# power_supplies.net
KiCad netlist of a schematic drawn in Altium Designer
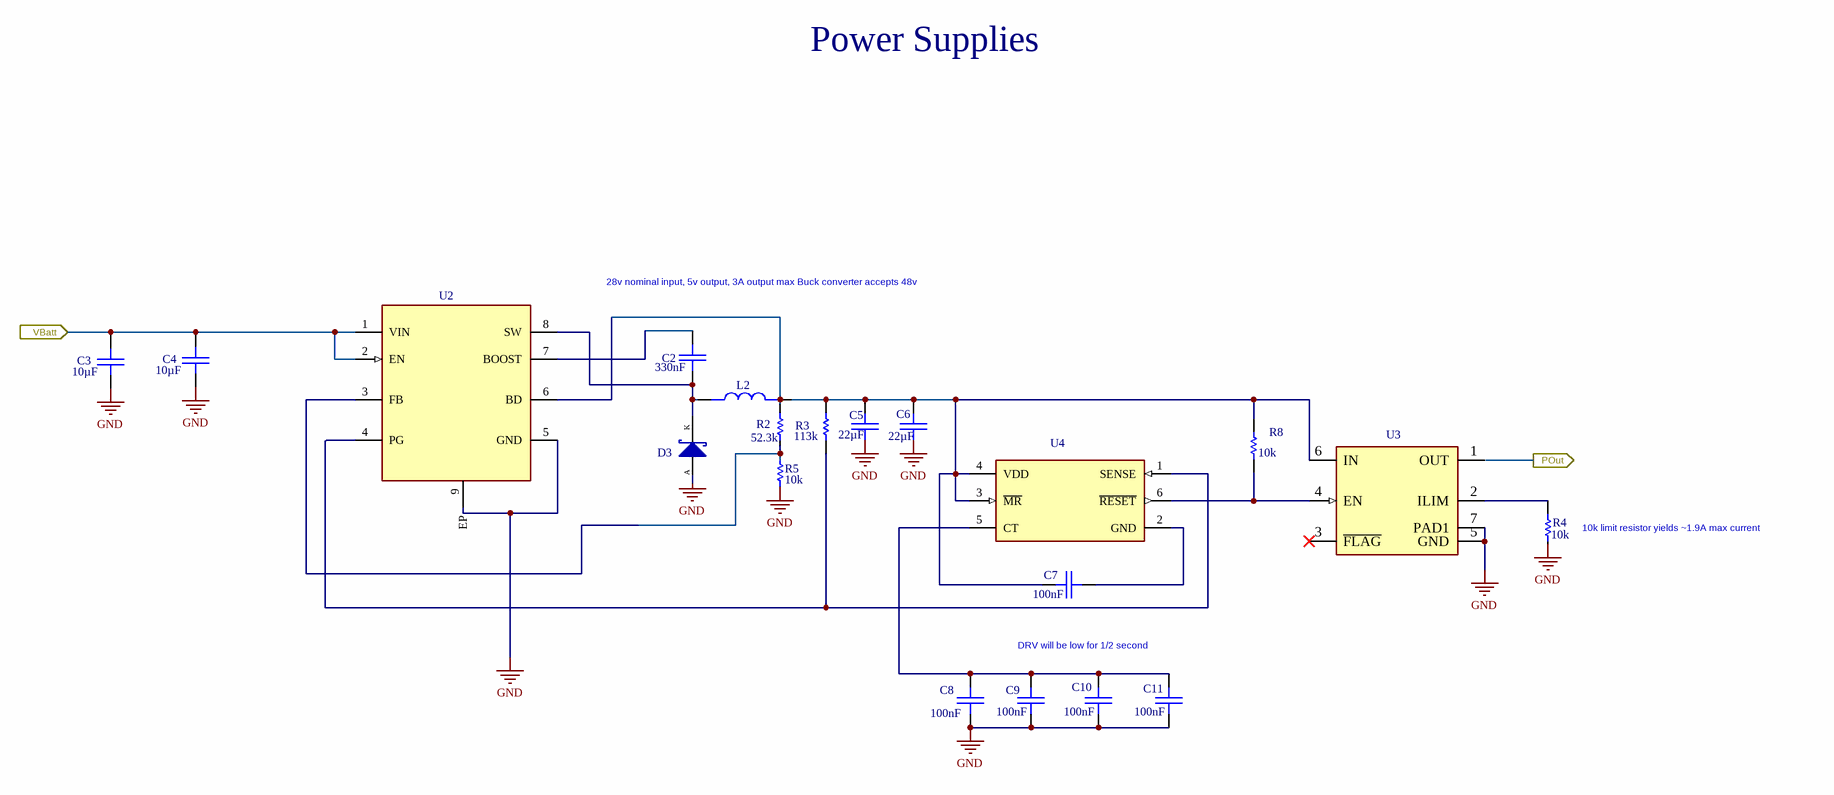
[diagram p0: power_supplies.SchDoc]

(export (version "E")
  (design (tool "Eeschema 10.0.6"))
  (components
    (comp (ref "C2")
      (value "330nF")
      (footprint "CAP-0805-A")
      (description "CAP 0805 0.33uF 50V 10% X7R CER")
      (fields (field (name "TOLERANCE") "10%"))
      (libsource (lib "Picatinny Server") (part "Capacitor - Non-Polarized"))
    )
    (comp (ref "C3")
      (value "10µF")
      (footprint "CAP-0805-A")
      (description "CAP 0805 10UF 50V 10% X5R")
      (libsource (lib "Picatinny Server") (part "Capacitor - Non-Polarized"))
    )
    (comp (ref "C4")
      (value "10µF")
      (footprint "CAP-0805-A")
      (description "CAP 0805 10UF 50V 10% X5R")
      (libsource (lib "Picatinny Server") (part "Capacitor - Non-Polarized"))
    )
    (comp (ref "C5")
      (value "22µF")
      (footprint "CAP-0805-C")
      (description "CAP 0805 22UF 16V 20% X5R")
      (libsource (lib "Picatinny Server") (part "Capacitor - Non-Polarized"))
    )
    (comp (ref "C6")
      (value "22µF")
      (footprint "CAP-0805-C")
      (description "CAP 0805 22UF 16V 20% X5R")
      (libsource (lib "Picatinny Server") (part "Capacitor - Non-Polarized"))
    )
    (comp (ref "C7")
      (value "100nF")
      (footprint "CAP-0402-A")
      (description "Multilayer Ceramic Capacitor, 0.1 uF, 25 V, ± 10%, X7R, 0402 [1005 Metric]")
      (fields (field (name "VOLTAGE") "25V") (field (name "Comment") "Cap 0402 0.1uf 25V 10% X7R"))
      (libsource (lib "Picatinny Server") (part "Capacitor - Non-Polarized"))
    )
    (comp (ref "C8")
      (value "100nF")
      (footprint "CAP-0402-A")
      (description "Multilayer Ceramic Capacitor, 0.1 uF, 25 V, ± 10%, X7R, 0402 [1005 Metric]")
      (fields (field (name "VOLTAGE") "25V") (field (name "Comment") "Cap 0402 0.1uf 25V 10% X7R"))
      (libsource (lib "Picatinny Server") (part "Capacitor - Non-Polarized"))
    )
    (comp (ref "C9")
      (value "100nF")
      (footprint "CAP-0402-A")
      (description "Multilayer Ceramic Capacitor, 0.1 uF, 25 V, ± 10%, X7R, 0402 [1005 Metric]")
      (fields (field (name "VOLTAGE") "25V") (field (name "Comment") "Cap 0402 0.1uf 25V 10% X7R"))
      (libsource (lib "Picatinny Server") (part "Capacitor - Non-Polarized"))
    )
    (comp (ref "C10")
      (value "100nF")
      (footprint "CAP-0402-A")
      (description "Multilayer Ceramic Capacitor, 0.1 uF, 25 V, ± 10%, X7R, 0402 [1005 Metric]")
      (fields (field (name "VOLTAGE") "25V") (field (name "Comment") "Cap 0402 0.1uf 25V 10% X7R"))
      (libsource (lib "Picatinny Server") (part "Capacitor - Non-Polarized"))
    )
    (comp (ref "C11")
      (value "100nF")
      (footprint "CAP-0402-A")
      (description "Multilayer Ceramic Capacitor, 0.1 uF, 25 V, ± 10%, X7R, 0402 [1005 Metric]")
      (fields (field (name "VOLTAGE") "25V") (field (name "Comment") "Cap 0402 0.1uf 25V 10% X7R"))
      (libsource (lib "Picatinny Server") (part "Capacitor - Non-Polarized"))
    )
    (comp (ref "D3")
      (value "SS3060HE_R1_00001")
      (footprint "DI-SOD123HE-A")
      (description "DIODE SCHOTTKY 60V 3A SOD123HE")
      (libsource (lib "Picatinny Server") (part "Diode - Schottky"))
    )
    (comp (ref "L2")
      (value "5-2176797-4")
      (footprint "IND-1210-A")
      (description "FIXED IND 2.2UH 3A 72 MOHM SMD")
      (libsource (lib "Picatinny Server") (part "Inductor"))
    )
    (comp (ref "R2")
      (value "52.3k")
      (footprint "RES-0402-C")
      (description "Res 0402 52.3K 1/10W 1% Thick Flim")
      (fields (field (name "TOLERANCE") "1%"))
      (libsource (lib "Picatinny Server") (part "Resistor"))
    )
    (comp (ref "R3")
      (value "113k")
      (footprint "RES-0402-C")
      (description "Res 0402 113K 1/10W 1% Thick Flim")
      (fields (field (name "TOLERANCE") "1%"))
      (libsource (lib "Picatinny Server") (part "Resistor"))
    )
    (comp (ref "R4")
      (value "10k")
      (footprint "RES-0402-A")
      (description "RES 0402 10K 1/10W 1%")
      (libsource (lib "Picatinny Server") (part "Resistor"))
    )
    (comp (ref "R5")
      (value "10k")
      (footprint "RES-0402-A")
      (description "RES 0402 10K 1/10W 1%")
      (libsource (lib "Picatinny Server") (part "Resistor"))
    )
    (comp (ref "R8")
      (value "10k")
      (footprint "RES-0402-A")
      (description "RES 0402 10K 1/10W 1%")
      (libsource (lib "Picatinny Server") (part "Resistor"))
    )
    (comp (ref "U2")
      (value "MCP16361T-E/NMX")
      (footprint "MCP16361T-E/NMX")
      (description "IC BUCK CONVERTER 48V 2MHZ")
      (libsource (lib "Picatinny Server") (part "MCP16361T-E/NMX"))
    )
    (comp (ref "U3")
      (value "NCP380HMUAJAAT")
      (footprint "IC-WDFN6-A")
      (description "Power Distribution Switch, Current-Limiting (Fixed and Adjustable) Adjustable, Enable H")
      (libsource (lib "Picatinny Server") (part "NCP380HMUAJAAT"))
    )
    (comp (ref "U4")
      (value "16399d4bb0613feb97433aaa3a53e95")
      (footprint "IC-WSON6-A")
      (description "Supervisor Open Drain or Open Collector 1 Channel 6-WSON (1.5x1.5)")
      (libsource (lib "Picatinny Server") (part "16399d4bb0613feb97433aaa3a53e95"))
    )
  )
  (nets
    (net (code "2") (name "/VBatt") (class "Default")
      (node (ref "C3") (pin "2") (pinfunction "2_2") (pintype "passive"))
      (node (ref "C4") (pin "2") (pinfunction "2_2") (pintype "passive"))
      (node (ref "U2") (pin "1") (pinfunction "VIN_1") (pintype "power_in"))
      (node (ref "U2") (pin "2") (pinfunction "EN_2") (pintype "input"))
    )
    (net (code "3") (name "GND") (class "Default")
      (node (ref "C10") (pin "1") (pinfunction "1_1") (pintype "passive"))
      (node (ref "C11") (pin "1") (pinfunction "1_1") (pintype "passive"))
      (node (ref "C3") (pin "1") (pinfunction "1_1") (pintype "passive"))
      (node (ref "C4") (pin "1") (pinfunction "1_1") (pintype "passive"))
      (node (ref "C8") (pin "1") (pinfunction "1_1") (pintype "passive"))
      (node (ref "C9") (pin "1") (pinfunction "1_1") (pintype "passive"))
      (node (ref "D3") (pin "A") (pinfunction "A_A") (pintype "passive"))
      (node (ref "U2") (pin "5") (pinfunction "GND_5") (pintype "power_in"))
      (node (ref "U3") (pin "5") (pinfunction "GND_5") (pintype "power_in"))
      (node (ref "U3") (pin "7") (pinfunction "PAD1_7") (pintype "passive"))
    )
    (net (code "4") (name "Net-(U2-BD)") (class "Default")
      (node (ref "R2") (pin "1") (pinfunction "1_1") (pintype "passive"))
      (node (ref "U2") (pin "6") (pinfunction "BD_6") (pintype "passive"))
    )
    (net (code "5") (name "Net-(U2-BOOST)") (class "Default")
      (node (ref "C2") (pin "2") (pinfunction "2_2") (pintype "passive"))
      (node (ref "U2") (pin "7") (pinfunction "BOOST_7") (pintype "passive"))
    )
    (net (code "6") (name "Net-(U2-FB)") (class "Default")
      (node (ref "R2") (pin "2") (pinfunction "2_2") (pintype "passive"))
      (node (ref "R5") (pin "2") (pinfunction "2_2") (pintype "passive"))
      (node (ref "U2") (pin "3") (pinfunction "FB_3") (pintype "passive"))
    )
    (net (code "7") (name "Net-(U2-PG)") (class "Default")
      (node (ref "R3") (pin "1") (pinfunction "1_1") (pintype "passive"))
      (node (ref "U2") (pin "4") (pinfunction "PG_4") (pintype "open_collector"))
      (node (ref "U4") (pin "1") (pinfunction "SENSE_1") (pintype "input"))
    )
    (net (code "8") (name "Net-(U2-SW)") (class "Default")
      (node (ref "C2") (pin "1") (pinfunction "1_1") (pintype "passive"))
      (node (ref "D3") (pin "K") (pinfunction "K_K") (pintype "passive"))
      (node (ref "L2") (pin "1") (pinfunction "1_1") (pintype "passive"))
      (node (ref "U2") (pin "8") (pinfunction "SW_8") (pintype "passive"))
    )
    (net (code "9") (name "Net-(U3-EN)") (class "Default")
      (node (ref "R8") (pin "1") (pinfunction "1_1") (pintype "passive"))
      (node (ref "U3") (pin "4") (pinfunction "EN_4") (pintype "input"))
      (node (ref "U4") (pin "6") (pinfunction "~{RESET}_6") (pintype "output"))
    )
    (net (code "10") (name "Net-(U3-ILIM)") (class "Default")
      (node (ref "R4") (pin "2") (pinfunction "2_2") (pintype "passive"))
      (node (ref "U3") (pin "2") (pinfunction "ILIM_2") (pintype "passive"))
    )
    (net (code "11") (name "Net-(U3-IN)") (class "Default")
      (node (ref "C5") (pin "2") (pinfunction "2_2") (pintype "passive"))
      (node (ref "C6") (pin "2") (pinfunction "2_2") (pintype "passive"))
      (node (ref "C7") (pin "1") (pinfunction "1_1") (pintype "passive"))
      (node (ref "L2") (pin "2") (pinfunction "2_2") (pintype "passive"))
      (node (ref "R3") (pin "2") (pinfunction "2_2") (pintype "passive"))
      (node (ref "R8") (pin "2") (pinfunction "2_2") (pintype "passive"))
      (node (ref "U3") (pin "6") (pinfunction "IN_6") (pintype "power_in"))
      (node (ref "U4") (pin "3") (pinfunction "~{MR}_3") (pintype "input"))
      (node (ref "U4") (pin "4") (pinfunction "VDD_4") (pintype "power_in"))
    )
    (net (code "12") (name "Net-(U4-CT)") (class "Default")
      (node (ref "C10") (pin "2") (pinfunction "2_2") (pintype "passive"))
      (node (ref "C11") (pin "2") (pinfunction "2_2") (pintype "passive"))
      (node (ref "C8") (pin "2") (pinfunction "2_2") (pintype "passive"))
      (node (ref "C9") (pin "2") (pinfunction "2_2") (pintype "passive"))
      (node (ref "U4") (pin "5") (pinfunction "CT_5") (pintype "passive"))
    )
    (net (code "13") (name "Net-(U4-GND)") (class "Default")
      (node (ref "C7") (pin "2") (pinfunction "2_2") (pintype "passive"))
      (node (ref "U4") (pin "2") (pinfunction "GND_2") (pintype "power_in"))
    )
    (net (code "14") (name "unconnected-(C5-Pad1)") (class "Default")
      (node (ref "C5") (pin "1") (pinfunction "1_1") (pintype "passive"))
    )
    (net (code "15") (name "unconnected-(C6-Pad1)") (class "Default")
      (node (ref "C6") (pin "1") (pinfunction "1_1") (pintype "passive"))
    )
    (net (code "16") (name "unconnected-(R4-Pad1)") (class "Default")
      (node (ref "R4") (pin "1") (pinfunction "1_1") (pintype "passive"))
    )
    (net (code "17") (name "unconnected-(R5-Pad1)") (class "Default")
      (node (ref "R5") (pin "1") (pinfunction "1_1") (pintype "passive"))
    )
    (net (code "18") (name "unconnected-(U2-EP-Pad9)") (class "Default")
      (node (ref "U2") (pin "9") (pinfunction "EP_9") (pintype "passive"))
    )
    (net (code "19") (name "unconnected-(U3-OUT-Pad1)") (class "Default")
      (node (ref "U3") (pin "1") (pinfunction "OUT_1") (pintype "power_in"))
    )
    (net (code "20") (name "unconnected-(U3-~{FLAG}-Pad3)") (class "Default")
      (node (ref "U3") (pin "3") (pinfunction "~{FLAG}_3") (pintype "open_collector+no_connect"))
    )
  )
)
